# slice2.net
KiCad netlist of a schematic drawn in EAGLE
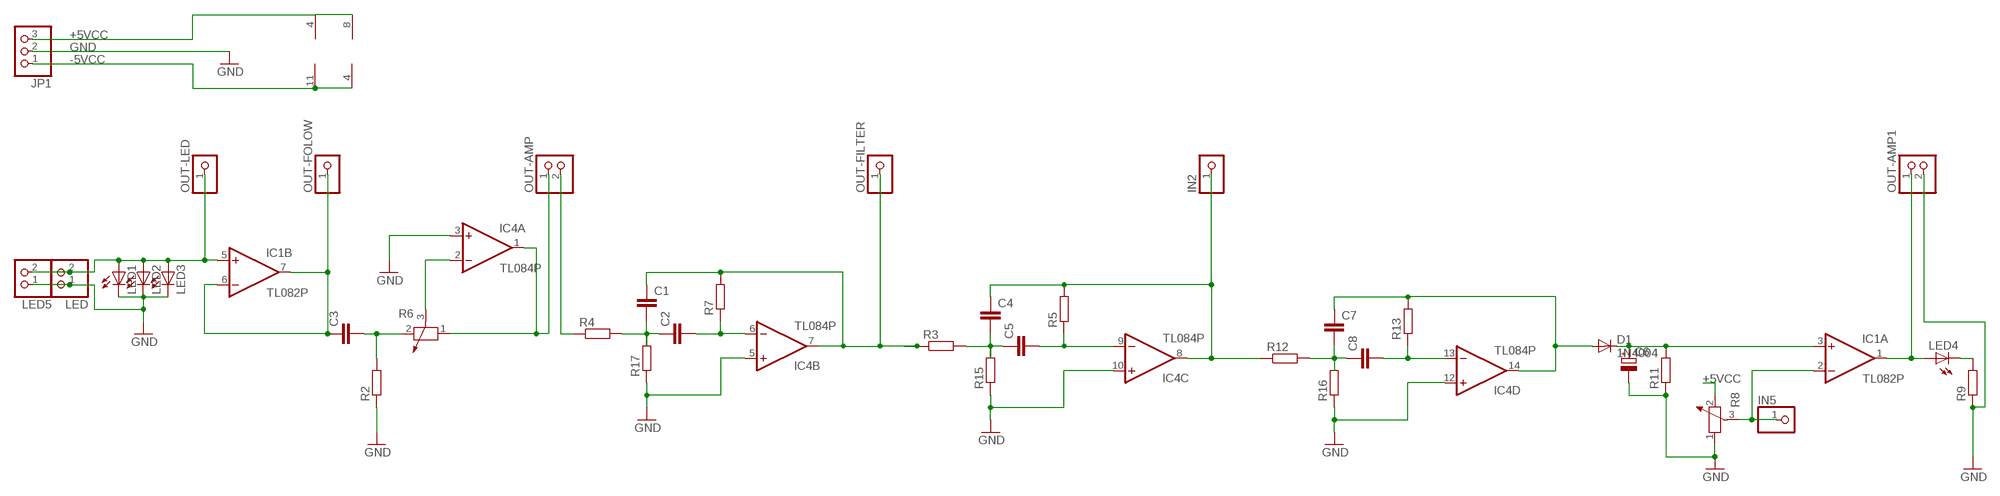
[diagram p0: schematic, sheet 1]

(export (version "E")
  (design (tool "Eeschema 10.0.6"))
  (components
    (comp (ref "C1")
      (value "C-EU050-024X044")
      (footprint "eagle-import:C050-024X044")
      (libsource (lib "eagle-import") (part "C-EU050-024X044"))
    )
    (comp (ref "C2")
      (value "C-EU050-024X044")
      (footprint "eagle-import:C050-024X044")
      (libsource (lib "eagle-import") (part "C-EU050-024X044"))
    )
    (comp (ref "C3")
      (value "C-EU050-024X044")
      (footprint "eagle-import:C050-024X044")
      (libsource (lib "eagle-import") (part "C-EU050-024X044"))
    )
    (comp (ref "C4")
      (value "C-EU050-024X044")
      (footprint "eagle-import:C050-024X044")
      (libsource (lib "eagle-import") (part "C-EU050-024X044"))
    )
    (comp (ref "C5")
      (value "C-EU050-024X044")
      (footprint "eagle-import:C050-024X044")
      (libsource (lib "eagle-import") (part "C-EU050-024X044"))
    )
    (comp (ref "C6")
      (value "CPOL-EUE3.5-8")
      (footprint "eagle-import:E3,5-8")
      (libsource (lib "eagle-import") (part "CPOL-EUE3.5-8"))
    )
    (comp (ref "C7")
      (value "C-EU050-024X044")
      (footprint "eagle-import:C050-024X044")
      (libsource (lib "eagle-import") (part "C-EU050-024X044"))
    )
    (comp (ref "C8")
      (value "C-EU050-024X044")
      (footprint "eagle-import:C050-024X044")
      (libsource (lib "eagle-import") (part "C-EU050-024X044"))
    )
    (comp (ref "D1")
      (value "1N4004")
      (footprint "eagle-import:DO41-10")
      (libsource (lib "eagle-import") (part "1N4004"))
    )
    (comp (ref "IC1")
      (value "TL082P")
      (footprint "eagle-import:DIL08")
      (libsource (lib "eagle-import") (part "TL082P"))
    )
    (comp (ref "IC4")
      (value "TL084P")
      (footprint "eagle-import:DIL14")
      (libsource (lib "eagle-import") (part "TL084P"))
    )
    (comp (ref "IN2")
      (value "PINHD-1X1")
      (footprint "eagle-import:1X01")
      (libsource (lib "eagle-import") (part "PINHD-1X1"))
    )
    (comp (ref "IN5")
      (value "PINHD-1X1")
      (footprint "eagle-import:1X01")
      (libsource (lib "eagle-import") (part "PINHD-1X1"))
    )
    (comp (ref "JP1")
      (value "PINHD-1X3")
      (footprint "eagle-import:1X03")
      (libsource (lib "eagle-import") (part "PINHD-1X3"))
    )
    (comp (ref "LED")
      (value "PINHD-1X2")
      (footprint "eagle-import:1X02")
      (libsource (lib "eagle-import") (part "PINHD-1X2"))
    )
    (comp (ref "LED1")
      (value "LED5MM")
      (footprint "eagle-import:LED5MM")
      (libsource (lib "eagle-import") (part "LED5MM"))
    )
    (comp (ref "LED2")
      (value "LED5MM")
      (footprint "eagle-import:LED5MM")
      (libsource (lib "eagle-import") (part "LED5MM"))
    )
    (comp (ref "LED3")
      (value "LED5MM")
      (footprint "eagle-import:LED5MM")
      (libsource (lib "eagle-import") (part "LED5MM"))
    )
    (comp (ref "LED4")
      (value "LED5MM")
      (footprint "eagle-import:LED5MM")
      (libsource (lib "eagle-import") (part "LED5MM"))
    )
    (comp (ref "LED5")
      (value "PINHD-1X2")
      (footprint "eagle-import:1X02")
      (libsource (lib "eagle-import") (part "PINHD-1X2"))
    )
    (comp (ref "OUT-AMP")
      (value "PINHD-1X2")
      (footprint "eagle-import:1X02")
      (libsource (lib "eagle-import") (part "PINHD-1X2"))
    )
    (comp (ref "OUT-AMP1")
      (value "PINHD-1X2")
      (footprint "eagle-import:1X02")
      (libsource (lib "eagle-import") (part "PINHD-1X2"))
    )
    (comp (ref "OUT-FILTER")
      (value "PINHD-1X1")
      (footprint "eagle-import:1X01")
      (libsource (lib "eagle-import") (part "PINHD-1X1"))
    )
    (comp (ref "OUT-FOLOW")
      (value "PINHD-1X1")
      (footprint "eagle-import:1X01")
      (libsource (lib "eagle-import") (part "PINHD-1X1"))
    )
    (comp (ref "OUT-LED")
      (value "PINHD-1X1")
      (footprint "eagle-import:1X01")
      (libsource (lib "eagle-import") (part "PINHD-1X1"))
    )
    (comp (ref "R2")
      (value "R-EU_0204/7")
      (footprint "eagle-import:0204_7")
      (libsource (lib "eagle-import") (part "R-EU_0204/7"))
    )
    (comp (ref "R3")
      (value "R-EU_0204/7")
      (footprint "eagle-import:0204_7")
      (libsource (lib "eagle-import") (part "R-EU_0204/7"))
    )
    (comp (ref "R4")
      (value "R-EU_0204/7")
      (footprint "eagle-import:0204_7")
      (libsource (lib "eagle-import") (part "R-EU_0204/7"))
    )
    (comp (ref "R5")
      (value "R-EU_0204/7")
      (footprint "eagle-import:0204_7")
      (libsource (lib "eagle-import") (part "R-EU_0204/7"))
    )
    (comp (ref "R6")
      (value "POTENTIOMETER_PT-10")
      (footprint "eagle-import:PT-10")
      (libsource (lib "eagle-import") (part "POTENTIOMETER_PT-10"))
    )
    (comp (ref "R7")
      (value "R-EU_0204/7")
      (footprint "eagle-import:0204_7")
      (libsource (lib "eagle-import") (part "R-EU_0204/7"))
    )
    (comp (ref "R8")
      (value "POTENTIOMETER_PT-10")
      (footprint "eagle-import:PT-10")
      (libsource (lib "eagle-import") (part "POTENTIOMETER_PT-10"))
    )
    (comp (ref "R9")
      (value "R-EU_0204/7")
      (footprint "eagle-import:0204_7")
      (libsource (lib "eagle-import") (part "R-EU_0204/7"))
    )
    (comp (ref "R11")
      (value "R-EU_0204/7")
      (footprint "eagle-import:0204_7")
      (libsource (lib "eagle-import") (part "R-EU_0204/7"))
    )
    (comp (ref "R12")
      (value "R-EU_0204/7")
      (footprint "eagle-import:0204_7")
      (libsource (lib "eagle-import") (part "R-EU_0204/7"))
    )
    (comp (ref "R13")
      (value "R-EU_0204/7")
      (footprint "eagle-import:0204_7")
      (libsource (lib "eagle-import") (part "R-EU_0204/7"))
    )
    (comp (ref "R15")
      (value "R-EU_0204/7")
      (footprint "eagle-import:0204_7")
      (libsource (lib "eagle-import") (part "R-EU_0204/7"))
    )
    (comp (ref "R16")
      (value "R-EU_0204/7")
      (footprint "eagle-import:0204_7")
      (libsource (lib "eagle-import") (part "R-EU_0204/7"))
    )
    (comp (ref "R17")
      (value "R-EU_0204/7")
      (footprint "eagle-import:0204_7")
      (libsource (lib "eagle-import") (part "R-EU_0204/7"))
    )
  )
  (nets
    (net (code "1") (name "/+5VCC") (class "Default")
      (node (ref "IC1") (pin "8") (pinfunction "V+_8") (pintype "power_in"))
      (node (ref "IC4") (pin "4") (pinfunction "V+_4") (pintype "power_in"))
      (node (ref "JP1") (pin "3") (pinfunction "3_3") (pintype "passive"))
      (node (ref "R8") (pin "2") (pinfunction "2_2") (pintype "passive"))
    )
    (net (code "2") (name "/-5VCC") (class "Default")
      (node (ref "IC1") (pin "4") (pinfunction "V-_4") (pintype "power_in"))
      (node (ref "IC4") (pin "11") (pinfunction "V-_11") (pintype "power_in"))
      (node (ref "JP1") (pin "1") (pinfunction "1_1") (pintype "passive"))
    )
    (net (code "3") (name "GND") (class "Default")
      (node (ref "C6") (pin "-") (pinfunction "-_-") (pintype "passive"))
      (node (ref "IC4") (pin "10") (pinfunction "+IN_10") (pintype "input"))
      (node (ref "IC4") (pin "12") (pinfunction "+IN_12") (pintype "input"))
      (node (ref "IC4") (pin "3") (pinfunction "+IN_3") (pintype "input"))
      (node (ref "IC4") (pin "5") (pinfunction "+IN_5") (pintype "input"))
      (node (ref "JP1") (pin "2") (pinfunction "2_2") (pintype "passive"))
      (node (ref "LED") (pin "1") (pinfunction "1_1") (pintype "passive"))
      (node (ref "LED1") (pin "K") (pinfunction "C_K") (pintype "passive"))
      (node (ref "LED2") (pin "K") (pinfunction "C_K") (pintype "passive"))
      (node (ref "LED3") (pin "K") (pinfunction "C_K") (pintype "passive"))
      (node (ref "LED5") (pin "1") (pinfunction "1_1") (pintype "passive"))
      (node (ref "OUT-AMP1") (pin "2") (pinfunction "2_2") (pintype "passive"))
      (node (ref "R11") (pin "1") (pinfunction "1_1") (pintype "passive"))
      (node (ref "R15") (pin "1") (pinfunction "1_1") (pintype "passive"))
      (node (ref "R16") (pin "1") (pinfunction "1_1") (pintype "passive"))
      (node (ref "R17") (pin "1") (pinfunction "1_1") (pintype "passive"))
      (node (ref "R2") (pin "1") (pinfunction "1_1") (pintype "passive"))
      (node (ref "R8") (pin "1") (pinfunction "1_1") (pintype "passive"))
      (node (ref "R9") (pin "1") (pinfunction "1_1") (pintype "passive"))
    )
    (net (code "4") (name "Net-(C1-Pad2)") (class "Default")
      (node (ref "C1") (pin "2") (pinfunction "2_2") (pintype "passive"))
      (node (ref "C2") (pin "1") (pinfunction "1_1") (pintype "passive"))
      (node (ref "R17") (pin "2") (pinfunction "2_2") (pintype "passive"))
      (node (ref "R4") (pin "2") (pinfunction "2_2") (pintype "passive"))
    )
    (net (code "5") (name "Net-(C3-Pad2)") (class "Default")
      (node (ref "C3") (pin "2") (pinfunction "2_2") (pintype "passive"))
      (node (ref "R2") (pin "2") (pinfunction "2_2") (pintype "passive"))
      (node (ref "R6") (pin "2") (pinfunction "2_2") (pintype "passive"))
    )
    (net (code "6") (name "Net-(C4-Pad2)") (class "Default")
      (node (ref "C4") (pin "2") (pinfunction "2_2") (pintype "passive"))
      (node (ref "C5") (pin "1") (pinfunction "1_1") (pintype "passive"))
      (node (ref "R15") (pin "2") (pinfunction "2_2") (pintype "passive"))
      (node (ref "R3") (pin "2") (pinfunction "2_2") (pintype "passive"))
    )
    (net (code "7") (name "Net-(C7-Pad2)") (class "Default")
      (node (ref "C7") (pin "2") (pinfunction "2_2") (pintype "passive"))
      (node (ref "C8") (pin "1") (pinfunction "1_1") (pintype "passive"))
      (node (ref "R12") (pin "2") (pinfunction "2_2") (pintype "passive"))
      (node (ref "R16") (pin "2") (pinfunction "2_2") (pintype "passive"))
    )
    (net (code "8") (name "Net-(IC1A-+IN)") (class "Default")
      (node (ref "C6") (pin "+") (pinfunction "+_+") (pintype "passive"))
      (node (ref "D1") (pin "C") (pinfunction "C_C") (pintype "passive"))
      (node (ref "IC1") (pin "3") (pinfunction "+IN_3") (pintype "input"))
      (node (ref "R11") (pin "2") (pinfunction "2_2") (pintype "passive"))
    )
    (net (code "9") (name "Net-(IC1A--IN)") (class "Default")
      (node (ref "IC1") (pin "2") (pinfunction "-IN_2") (pintype "input"))
      (node (ref "IN5") (pin "1") (pinfunction "1_1") (pintype "passive"))
      (node (ref "R8") (pin "3") (pinfunction "3_3") (pintype "passive"))
    )
    (net (code "10") (name "Net-(IC1A-OUT)") (class "Default")
      (node (ref "IC1") (pin "1") (pinfunction "OUT_1") (pintype "output"))
      (node (ref "LED4") (pin "A") (pinfunction "A_A") (pintype "passive"))
      (node (ref "OUT-AMP1") (pin "1") (pinfunction "1_1") (pintype "passive"))
    )
    (net (code "11") (name "Net-(IC1B-+IN)") (class "Default")
      (node (ref "IC1") (pin "5") (pinfunction "+IN_5") (pintype "input"))
      (node (ref "LED") (pin "2") (pinfunction "2_2") (pintype "passive"))
      (node (ref "LED1") (pin "A") (pinfunction "A_A") (pintype "passive"))
      (node (ref "LED2") (pin "A") (pinfunction "A_A") (pintype "passive"))
      (node (ref "LED3") (pin "A") (pinfunction "A_A") (pintype "passive"))
      (node (ref "LED5") (pin "2") (pinfunction "2_2") (pintype "passive"))
      (node (ref "OUT-LED") (pin "1") (pinfunction "1_1") (pintype "passive"))
    )
    (net (code "12") (name "Net-(IC1B--IN)") (class "Default")
      (node (ref "C3") (pin "1") (pinfunction "1_1") (pintype "passive"))
      (node (ref "IC1") (pin "6") (pinfunction "-IN_6") (pintype "input"))
      (node (ref "IC1") (pin "7") (pinfunction "OUT_7") (pintype "output"))
      (node (ref "OUT-FOLOW") (pin "1") (pinfunction "1_1") (pintype "passive"))
    )
    (net (code "13") (name "Net-(IC4A--IN)") (class "Default")
      (node (ref "IC4") (pin "2") (pinfunction "-IN_2") (pintype "input"))
      (node (ref "R6") (pin "3") (pinfunction "3_3") (pintype "passive"))
    )
    (net (code "14") (name "Net-(IC4A-OUT)") (class "Default")
      (node (ref "IC4") (pin "1") (pinfunction "OUT_1") (pintype "output"))
      (node (ref "OUT-AMP") (pin "1") (pinfunction "1_1") (pintype "passive"))
      (node (ref "R6") (pin "1") (pinfunction "1_1") (pintype "passive"))
    )
    (net (code "15") (name "Net-(IC4B--IN)") (class "Default")
      (node (ref "C2") (pin "2") (pinfunction "2_2") (pintype "passive"))
      (node (ref "IC4") (pin "6") (pinfunction "-IN_6") (pintype "input"))
      (node (ref "R7") (pin "1") (pinfunction "1_1") (pintype "passive"))
    )
    (net (code "16") (name "Net-(IC4B-OUT)") (class "Default")
      (node (ref "C1") (pin "1") (pinfunction "1_1") (pintype "passive"))
      (node (ref "IC4") (pin "7") (pinfunction "OUT_7") (pintype "output"))
      (node (ref "OUT-FILTER") (pin "1") (pinfunction "1_1") (pintype "passive"))
      (node (ref "R3") (pin "1") (pinfunction "1_1") (pintype "passive"))
      (node (ref "R7") (pin "2") (pinfunction "2_2") (pintype "passive"))
    )
    (net (code "17") (name "Net-(IC4C--IN)") (class "Default")
      (node (ref "C5") (pin "2") (pinfunction "2_2") (pintype "passive"))
      (node (ref "IC4") (pin "9") (pinfunction "-IN_9") (pintype "input"))
      (node (ref "R5") (pin "1") (pinfunction "1_1") (pintype "passive"))
    )
    (net (code "18") (name "Net-(IC4C-OUT)") (class "Default")
      (node (ref "C4") (pin "1") (pinfunction "1_1") (pintype "passive"))
      (node (ref "IC4") (pin "8") (pinfunction "OUT_8") (pintype "output"))
      (node (ref "IN2") (pin "1") (pinfunction "1_1") (pintype "passive"))
      (node (ref "R12") (pin "1") (pinfunction "1_1") (pintype "passive"))
      (node (ref "R5") (pin "2") (pinfunction "2_2") (pintype "passive"))
    )
    (net (code "19") (name "Net-(IC4D--IN)") (class "Default")
      (node (ref "C8") (pin "2") (pinfunction "2_2") (pintype "passive"))
      (node (ref "IC4") (pin "13") (pinfunction "-IN_13") (pintype "input"))
      (node (ref "R13") (pin "1") (pinfunction "1_1") (pintype "passive"))
    )
    (net (code "20") (name "Net-(IC4D-OUT)") (class "Default")
      (node (ref "C7") (pin "1") (pinfunction "1_1") (pintype "passive"))
      (node (ref "D1") (pin "A") (pinfunction "A_A") (pintype "passive"))
      (node (ref "IC4") (pin "14") (pinfunction "OUT_14") (pintype "output"))
      (node (ref "R13") (pin "2") (pinfunction "2_2") (pintype "passive"))
    )
    (net (code "21") (name "Net-(LED4-C)") (class "Default")
      (node (ref "LED4") (pin "K") (pinfunction "C_K") (pintype "passive"))
      (node (ref "R9") (pin "2") (pinfunction "2_2") (pintype "passive"))
    )
    (net (code "22") (name "Net-(OUT-AMP-Pad2)") (class "Default")
      (node (ref "OUT-AMP") (pin "2") (pinfunction "2_2") (pintype "passive"))
      (node (ref "R4") (pin "1") (pinfunction "1_1") (pintype "passive"))
    )
  )
)
